# Sensors.net
KiCad netlist of a schematic drawn in Altium Designer
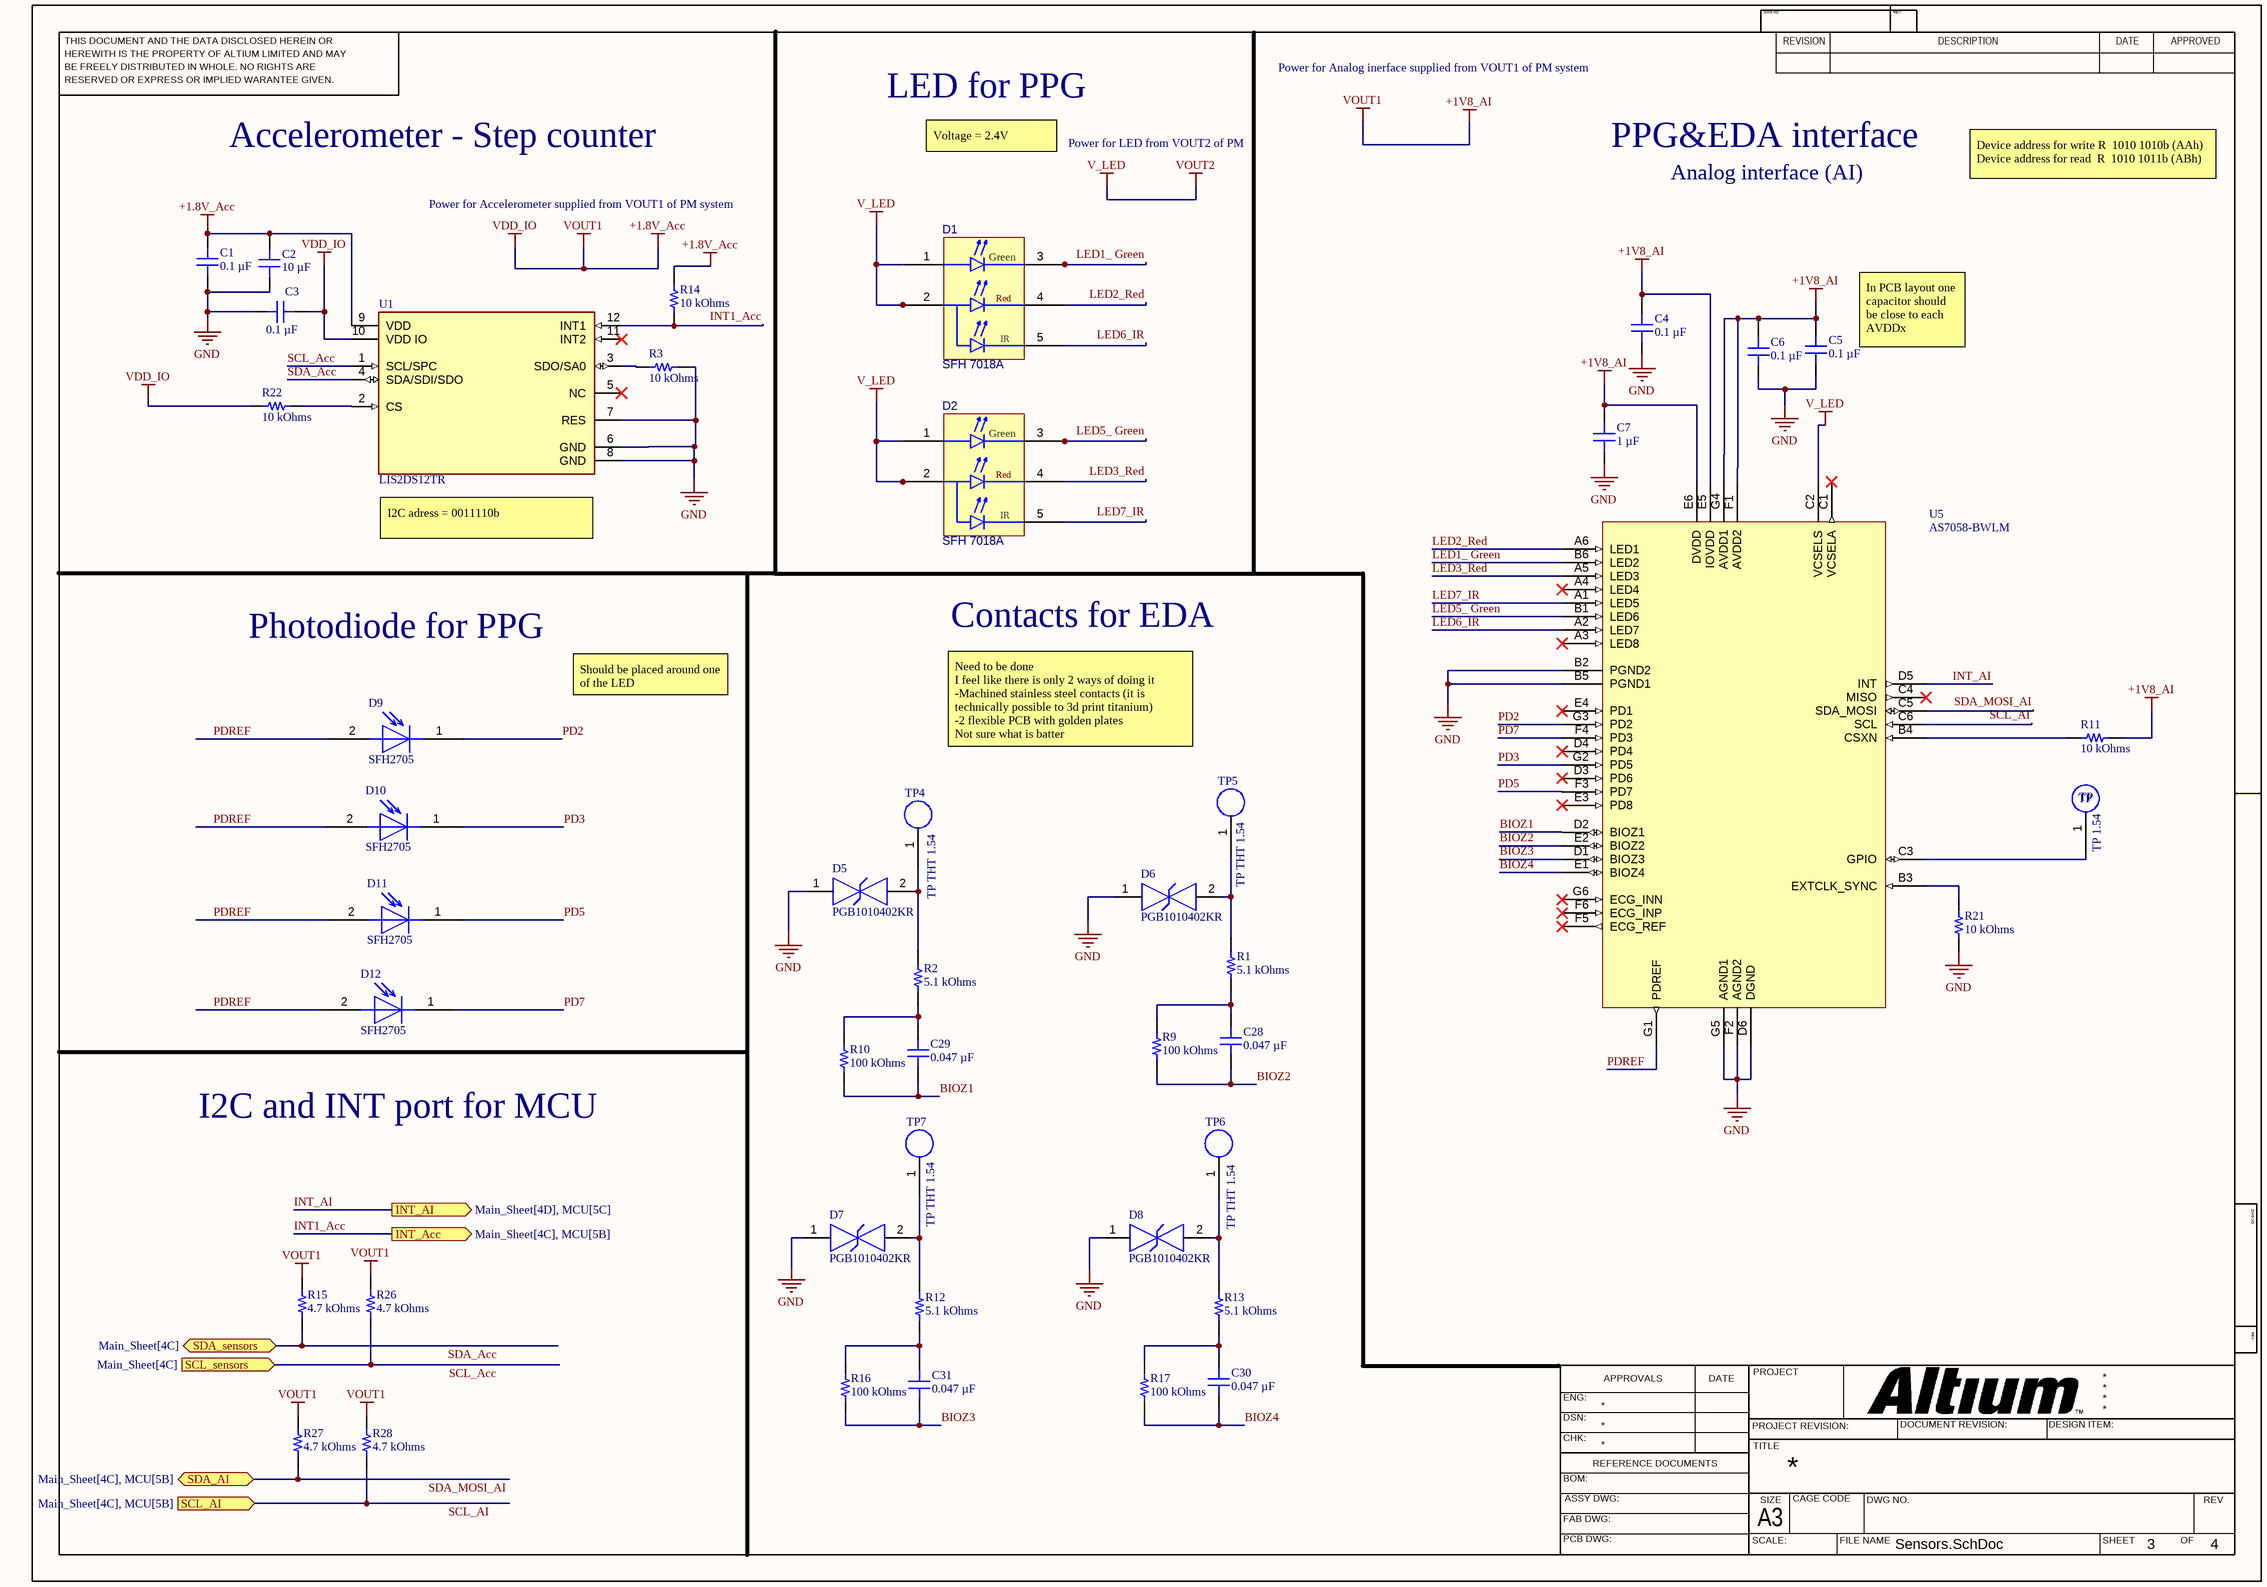
[diagram p0: Sensors.SchDoc]

(export (version "E")
  (design (tool "Eeschema 10.0.6"))
  (components
    (comp (ref "C1")
      (value "0.1 µF")
      (footprint "CAP 0402_1005")
      (description "CAP CER 100NF 10V X7R 0402")
      (fields
        (field (name "PART NUMBER") "CL05B104KP5VPNC")
        (field (name "CAPACITANCE") "0.1 µF")
        (field (name "MANUFACTURER") "Samsung Electro-Mechanics")
      )
      (libsource (lib "Celestial Altium Library - altium_library") (part "Capacitor"))
    )
    (comp (ref "C2")
      (value "10 µF")
      (footprint "CAP 0402_1005")
      (description "CAP CER 10UF 10V X5R 0402")
      (fields
        (field (name "PART NUMBER") "CL05A106MP8NUB8")
        (field (name "CAPACITANCE") "10 µF")
        (field (name "MANUFACTURER") "Samsung Electro-Mechanics")
      )
      (libsource (lib "Celestial Altium Library - altium_library") (part "Capacitor"))
    )
    (comp (ref "C3")
      (value "0.1 µF")
      (footprint "CAP 0402_1005")
      (description "CAP CER 100NF 10V X7R 0402")
      (fields
        (field (name "PART NUMBER") "CL05B104KP5VPNC")
        (field (name "CAPACITANCE") "0.1 µF")
        (field (name "MANUFACTURER") "Samsung Electro-Mechanics")
      )
      (libsource (lib "Celestial Altium Library - altium_library") (part "Capacitor"))
    )
    (comp (ref "C4")
      (value "0.1 µF")
      (footprint "CAP 0402_1005")
      (description "CAP CER 100NF 10V X7R 0402")
      (fields
        (field (name "PART NUMBER") "CL05B104KP5VPNC")
        (field (name "CAPACITANCE") "0.1 µF")
        (field (name "MANUFACTURER") "Samsung Electro-Mechanics")
      )
      (libsource (lib "Celestial Altium Library - altium_library") (part "Capacitor"))
    )
    (comp (ref "C5")
      (value "0.1 µF")
      (footprint "CAP 0402_1005")
      (description "CAP CER 100NF 10V X7R 0402")
      (fields
        (field (name "PART NUMBER") "CL05B104KP5VPNC")
        (field (name "CAPACITANCE") "0.1 µF")
        (field (name "MANUFACTURER") "Samsung Electro-Mechanics")
      )
      (libsource (lib "Celestial Altium Library - altium_library") (part "Capacitor"))
    )
    (comp (ref "C6")
      (value "0.1 µF")
      (footprint "CAP 0402_1005")
      (description "CAP CER 100NF 10V X7R 0402")
      (fields
        (field (name "PART NUMBER") "CL05B104KP5VPNC")
        (field (name "CAPACITANCE") "0.1 µF")
        (field (name "MANUFACTURER") "Samsung Electro-Mechanics")
      )
      (libsource (lib "Celestial Altium Library - altium_library") (part "Capacitor"))
    )
    (comp (ref "C7")
      (value "1 µF")
      (footprint "CAP 0402_1005")
      (description "CAP CER 1UF 10V X5R 0402")
      (fields
        (field (name "PART NUMBER") "885012105012")
        (field (name "CAPACITANCE") "1 µF")
        (field (name "MANUFACTURER") "Würth Elektronik")
      )
      (libsource (lib "Celestial Altium Library - altium_library") (part "Capacitor"))
    )
    (comp (ref "C28")
      (value "0.047 µF")
      (footprint "CAP 0402_1005")
      (description "CAP CER 0402 47NF 25V X7R 10%")
      (fields
        (field (name "PART NUMBER") "C0402C473K3REC7867")
        (field (name "CAPACITANCE") "0.047 µF")
        (field (name "MANUFACTURER") "KEMET")
      )
      (libsource (lib "Celestial Altium Library - altium_library") (part "Capacitor"))
    )
    (comp (ref "C29")
      (value "0.047 µF")
      (footprint "CAP 0402_1005")
      (description "CAP CER 0402 47NF 25V X7R 10%")
      (fields
        (field (name "PART NUMBER") "C0402C473K3REC7867")
        (field (name "CAPACITANCE") "0.047 µF")
        (field (name "MANUFACTURER") "KEMET")
      )
      (libsource (lib "Celestial Altium Library - altium_library") (part "Capacitor"))
    )
    (comp (ref "C30")
      (value "0.047 µF")
      (footprint "CAP 0402_1005")
      (description "CAP CER 0402 47NF 25V X7R 10%")
      (fields
        (field (name "PART NUMBER") "C0402C473K3REC7867")
        (field (name "CAPACITANCE") "0.047 µF")
        (field (name "MANUFACTURER") "KEMET")
      )
      (libsource (lib "Celestial Altium Library - altium_library") (part "Capacitor"))
    )
    (comp (ref "C31")
      (value "0.047 µF")
      (footprint "CAP 0402_1005")
      (description "CAP CER 0402 47NF 25V X7R 10%")
      (fields
        (field (name "PART NUMBER") "C0402C473K3REC7867")
        (field (name "CAPACITANCE") "0.047 µF")
        (field (name "MANUFACTURER") "KEMET")
      )
      (libsource (lib "Celestial Altium Library - altium_library") (part "Capacitor"))
    )
    (comp (ref "D1")
      (value "SFH 7018A")
      (footprint "SFH 7018A-Footprint-1")
      (description "Led, Hr/ir/tg, 655/940/532NM, 120DEG Rohs Compliant: Yes")
      (libsource (lib "Kiryl Alsheuski") (part "DIODE-LED-2"))
    )
    (comp (ref "D2")
      (value "SFH 7018A")
      (footprint "SFH 7018A-Footprint-1")
      (description "Led, Hr/ir/tg, 655/940/532NM, 120DEG Rohs Compliant: Yes")
      (libsource (lib "Kiryl Alsheuski") (part "DIODE-LED-2"))
    )
    (comp (ref "D5")
      (value "PGB1010402KR")
      (footprint "FP-PGB1-0402-MFG")
      (description "TVS DIODE 12V 250V 0402")
      (fields
        (field (name "OCTOPART") "https://octopart.com/pgb1010402kr-littelfuse-10444990")
        (field (name "MANUFACTURER") "Littelfuse")
      )
      (libsource (lib "Altium Content Vault") (part "876f4347bf90aa6f500f43e3cd03972"))
    )
    (comp (ref "D6")
      (value "PGB1010402KR")
      (footprint "FP-PGB1-0402-MFG")
      (description "TVS DIODE 12V 250V 0402")
      (fields
        (field (name "OCTOPART") "https://octopart.com/pgb1010402kr-littelfuse-10444990")
        (field (name "MANUFACTURER") "Littelfuse")
      )
      (libsource (lib "Altium Content Vault") (part "876f4347bf90aa6f500f43e3cd03972"))
    )
    (comp (ref "D7")
      (value "PGB1010402KR")
      (footprint "FP-PGB1-0402-MFG")
      (description "TVS DIODE 12V 250V 0402")
      (fields
        (field (name "OCTOPART") "https://octopart.com/pgb1010402kr-littelfuse-10444990")
        (field (name "MANUFACTURER") "Littelfuse")
      )
      (libsource (lib "Altium Content Vault") (part "876f4347bf90aa6f500f43e3cd03972"))
    )
    (comp (ref "D8")
      (value "PGB1010402KR")
      (footprint "FP-PGB1-0402-MFG")
      (description "TVS DIODE 12V 250V 0402")
      (fields
        (field (name "OCTOPART") "https://octopart.com/pgb1010402kr-littelfuse-10444990")
        (field (name "MANUFACTURER") "Littelfuse")
      )
      (libsource (lib "Altium Content Vault") (part "876f4347bf90aa6f500f43e3cd03972"))
    )
    (comp (ref "D9")
      (value "SFH2705")
      (footprint "DFN175P215X60-2N")
      (description "Photodiode with wide range of wavelength")
      (libsource (lib "Kiryl Alsheuski") (part "SFH2705-Symbol-1"))
    )
    (comp (ref "D10")
      (value "SFH2705")
      (footprint "DFN175P215X60-2N")
      (description "Photodiode with wide range of wavelength")
      (libsource (lib "Kiryl Alsheuski") (part "SFH2705-Symbol-1"))
    )
    (comp (ref "D11")
      (value "SFH2705")
      (footprint "DFN175P215X60-2N")
      (description "Photodiode with wide range of wavelength")
      (libsource (lib "Kiryl Alsheuski") (part "SFH2705-Symbol-1"))
    )
    (comp (ref "D12")
      (value "SFH2705")
      (footprint "DFN175P215X60-2N")
      (description "Photodiode with wide range of wavelength")
      (libsource (lib "Kiryl Alsheuski") (part "SFH2705-Symbol-1"))
    )
    (comp (ref "R1")
      (value "5.1 kOhms")
      (footprint "RES 0402_1005")
      (description "RES 5.1K OHM 1% 1/4W 0402")
      (fields
        (field (name "PART NUMBER") "ERJ-PA2F5101X")
        (field (name "MANUFACTURER") "Panasonic Electronic Components")
      )
      (libsource (lib "Celestial Altium Library - altium_library") (part "Resistor"))
    )
    (comp (ref "R2")
      (value "5.1 kOhms")
      (footprint "RES 0402_1005")
      (description "RES 5.1K OHM 1% 1/4W 0402")
      (fields
        (field (name "PART NUMBER") "ERJ-PA2F5101X")
        (field (name "MANUFACTURER") "Panasonic Electronic Components")
      )
      (libsource (lib "Celestial Altium Library - altium_library") (part "Resistor"))
    )
    (comp (ref "R3")
      (value "10 kOhms")
      (footprint "RES 0402_1005")
      (description "RES 10K OHM 0.1% 1/10W 0402")
      (fields
        (field (name "PART NUMBER") "RP73PF1E10KBTD")
        (field (name "MANUFACTURER") "TE Connectivity Passive Product")
      )
      (libsource (lib "Celestial Altium Library - altium_library") (part "Resistor"))
    )
    (comp (ref "R9")
      (value "100 kOhms")
      (footprint "YAGEO RES 0402_1005")
      (description "RES 100K OHM 1% 1/5W 0402")
      (fields (field (name "PART NUMBER") "SR0402FR-7T100KL") (field (name "MANUFACTURER") "Yageo"))
      (libsource (lib "Celestial Altium Library - altium_library") (part "Resistor"))
    )
    (comp (ref "R10")
      (value "100 kOhms")
      (footprint "YAGEO RES 0402_1005")
      (description "RES 100K OHM 1% 1/5W 0402")
      (fields (field (name "PART NUMBER") "SR0402FR-7T100KL") (field (name "MANUFACTURER") "Yageo"))
      (libsource (lib "Celestial Altium Library - altium_library") (part "Resistor"))
    )
    (comp (ref "R11")
      (value "10 kOhms")
      (footprint "RES 0402_1005")
      (description "RES 10K OHM 0.1% 1/10W 0402")
      (fields
        (field (name "PART NUMBER") "RP73PF1E10KBTD")
        (field (name "MANUFACTURER") "TE Connectivity Passive Product")
      )
      (libsource (lib "Celestial Altium Library - altium_library") (part "Resistor"))
    )
    (comp (ref "R12")
      (value "5.1 kOhms")
      (footprint "RES 0402_1005")
      (description "RES 5.1K OHM 1% 1/4W 0402")
      (fields
        (field (name "PART NUMBER") "ERJ-PA2F5101X")
        (field (name "MANUFACTURER") "Panasonic Electronic Components")
      )
      (libsource (lib "Celestial Altium Library - altium_library") (part "Resistor"))
    )
    (comp (ref "R13")
      (value "5.1 kOhms")
      (footprint "RES 0402_1005")
      (description "RES 5.1K OHM 1% 1/4W 0402")
      (fields
        (field (name "PART NUMBER") "ERJ-PA2F5101X")
        (field (name "MANUFACTURER") "Panasonic Electronic Components")
      )
      (libsource (lib "Celestial Altium Library - altium_library") (part "Resistor"))
    )
    (comp (ref "R14")
      (value "10 kOhms")
      (footprint "RES 0402_1005")
      (description "RES 10K OHM 0.1% 1/10W 0402")
      (fields
        (field (name "PART NUMBER") "RP73PF1E10KBTD")
        (field (name "MANUFACTURER") "TE Connectivity Passive Product")
      )
      (libsource (lib "Celestial Altium Library - altium_library") (part "Resistor"))
    )
    (comp (ref "R15")
      (value "4.7 kOhms")
      (footprint "YAGEO RES 0402_1005")
      (description "RES SMD 4.7K OHM 1% 1/16W 0402")
      (fields (field (name "PART NUMBER") "RT0402FRE074K7L") (field (name "MANUFACTURER") "Yageo"))
      (libsource (lib "Celestial Altium Library - altium_library") (part "Resistor"))
    )
    (comp (ref "R16")
      (value "100 kOhms")
      (footprint "YAGEO RES 0402_1005")
      (description "RES 100K OHM 1% 1/5W 0402")
      (fields (field (name "PART NUMBER") "SR0402FR-7T100KL") (field (name "MANUFACTURER") "Yageo"))
      (libsource (lib "Celestial Altium Library - altium_library") (part "Resistor"))
    )
    (comp (ref "R17")
      (value "100 kOhms")
      (footprint "YAGEO RES 0402_1005")
      (description "RES 100K OHM 1% 1/5W 0402")
      (fields (field (name "PART NUMBER") "SR0402FR-7T100KL") (field (name "MANUFACTURER") "Yageo"))
      (libsource (lib "Celestial Altium Library - altium_library") (part "Resistor"))
    )
    (comp (ref "R21")
      (value "10 kOhms")
      (footprint "RES 0402_1005")
      (description "RES 10K OHM 0.1% 1/10W 0402")
      (fields
        (field (name "PART NUMBER") "RP73PF1E10KBTD")
        (field (name "MANUFACTURER") "TE Connectivity Passive Product")
      )
      (libsource (lib "Celestial Altium Library - altium_library") (part "Resistor"))
    )
    (comp (ref "R22")
      (value "10 kOhms")
      (footprint "RES 0402_1005")
      (description "RES 10K OHM 0.1% 1/10W 0402")
      (fields
        (field (name "PART NUMBER") "RP73PF1E10KBTD")
        (field (name "MANUFACTURER") "TE Connectivity Passive Product")
      )
      (libsource (lib "Celestial Altium Library - altium_library") (part "Resistor"))
    )
    (comp (ref "R26")
      (value "4.7 kOhms")
      (footprint "YAGEO RES 0402_1005")
      (description "RES SMD 4.7K OHM 1% 1/16W 0402")
      (fields (field (name "PART NUMBER") "RT0402FRE074K7L") (field (name "MANUFACTURER") "Yageo"))
      (libsource (lib "Celestial Altium Library - altium_library") (part "Resistor"))
    )
    (comp (ref "R27")
      (value "4.7 kOhms")
      (footprint "YAGEO RES 0402_1005")
      (description "RES SMD 4.7K OHM 1% 1/16W 0402")
      (fields (field (name "PART NUMBER") "RT0402FRE074K7L") (field (name "MANUFACTURER") "Yageo"))
      (libsource (lib "Celestial Altium Library - altium_library") (part "Resistor"))
    )
    (comp (ref "R28")
      (value "4.7 kOhms")
      (footprint "YAGEO RES 0402_1005")
      (description "RES SMD 4.7K OHM 1% 1/16W 0402")
      (fields (field (name "PART NUMBER") "RT0402FRE074K7L") (field (name "MANUFACTURER") "Yageo"))
      (libsource (lib "Celestial Altium Library - altium_library") (part "Resistor"))
    )
    (comp (ref "TP")
      (value "TP 1.54")
      (footprint "TP-Footprint-1")
      (description "Rounded rectangular pad 1.54mm")
      (libsource (lib "Kiryl Alsheuski") (part "TP-Symbol-1"))
    )
    (comp (ref "TP4")
      (value "TP THT 1.54")
      (footprint "TP-Footprint-1")
      (description "Test pint THT round via 1.54mm pad 1mm hole")
      (libsource (lib "") (part "TP-Symbol-1_1"))
    )
    (comp (ref "TP5")
      (value "TP THT 1.54")
      (footprint "TP-Footprint-1")
      (description "Test pint THT round via 1.54mm pad 1mm hole")
      (libsource (lib "") (part "TP-Symbol-1_1"))
    )
    (comp (ref "TP6")
      (value "TP THT 1.54")
      (footprint "TP-Footprint-1")
      (description "Test pint THT round via 1.54mm pad 1mm hole")
      (libsource (lib "") (part "TP-Symbol-1_1"))
    )
    (comp (ref "TP7")
      (value "TP THT 1.54")
      (footprint "TP-Footprint-1")
      (description "Test pint THT round via 1.54mm pad 1mm hole")
      (libsource (lib "") (part "TP-Symbol-1_1"))
    )
    (comp (ref "U1")
      (value "LIS2DS12TR")
      (footprint "FP-LGA12_8566956-MFG")
      (description "ACCEL 2-16G I2C/SPI 12LGA")
      (libsource (lib "Altium Content Vault") (part "71777070b7db0ed8ebb1a0f678b9644"))
    )
    (comp (ref "U5")
      (value "AS7058-BWLM")
      (footprint "BGA42C40P6X7_254X282X60")
      (description "AS7058 Series 1.8 V PPG/ECG/BioZ/EDA Vital Sign Monitoring IC - WLCSP-42")
      (libsource (lib "Kiryl Alsheuski") (part "AS7058-BWLM-Symbol-1"))
    )
  )
  (nets
    (net (code "1") (name "+1.8V_Acc") (class "Default")
      (node (ref "C1") (pin "2") (pinfunction "2_2") (pintype "passive"))
      (node (ref "C2") (pin "2") (pinfunction "2_2") (pintype "passive"))
      (node (ref "C3") (pin "1") (pinfunction "1_1") (pintype "passive"))
      (node (ref "C4") (pin "2") (pinfunction "2_2") (pintype "passive"))
      (node (ref "C5") (pin "2") (pinfunction "2_2") (pintype "passive"))
      (node (ref "C6") (pin "2") (pinfunction "2_2") (pintype "passive"))
      (node (ref "C7") (pin "2") (pinfunction "2_2") (pintype "passive"))
      (node (ref "R11") (pin "2") (pinfunction "2_2") (pintype "passive"))
      (node (ref "R14") (pin "2") (pinfunction "2_2") (pintype "passive"))
      (node (ref "R15") (pin "2") (pinfunction "2_2") (pintype "passive"))
      (node (ref "R22") (pin "1") (pinfunction "1_1") (pintype "passive"))
      (node (ref "R26") (pin "2") (pinfunction "2_2") (pintype "passive"))
      (node (ref "R27") (pin "2") (pinfunction "2_2") (pintype "passive"))
      (node (ref "R28") (pin "2") (pinfunction "2_2") (pintype "passive"))
      (node (ref "U1") (pin "10") (pinfunction "VDD_IO_10") (pintype "power_in"))
      (node (ref "U1") (pin "9") (pinfunction "VDD_9") (pintype "power_in"))
      (node (ref "U5") (pin "E5") (pinfunction "IOVDD_E5") (pintype "power_in"))
      (node (ref "U5") (pin "E6") (pinfunction "DVDD_E6") (pintype "power_in"))
      (node (ref "U5") (pin "F1") (pinfunction "AVDD2_F1") (pintype "power_in"))
      (node (ref "U5") (pin "G4") (pinfunction "AVDD1_G4") (pintype "power_in"))
    )
    (net (code "2") (name "/BIOZ1") (class "Default")
      (node (ref "C29") (pin "1") (pinfunction "1_1") (pintype "passive"))
      (node (ref "R10") (pin "1") (pinfunction "1_1") (pintype "passive"))
      (node (ref "U5") (pin "D2") (pinfunction "BIOZ1_D2") (pintype "bidirectional"))
    )
    (net (code "3") (name "/BIOZ2") (class "Default")
      (node (ref "C28") (pin "1") (pinfunction "1_1") (pintype "passive"))
      (node (ref "R9") (pin "1") (pinfunction "1_1") (pintype "passive"))
      (node (ref "U5") (pin "E2") (pinfunction "BIOZ2_E2") (pintype "bidirectional"))
    )
    (net (code "4") (name "/BIOZ3") (class "Default")
      (node (ref "C31") (pin "1") (pinfunction "1_1") (pintype "passive"))
      (node (ref "R16") (pin "1") (pinfunction "1_1") (pintype "passive"))
      (node (ref "U5") (pin "D1") (pinfunction "BIOZ3_D1") (pintype "bidirectional"))
    )
    (net (code "5") (name "/BIOZ4") (class "Default")
      (node (ref "C30") (pin "1") (pinfunction "1_1") (pintype "passive"))
      (node (ref "R17") (pin "1") (pinfunction "1_1") (pintype "passive"))
      (node (ref "U5") (pin "E1") (pinfunction "BIOZ4_E1") (pintype "bidirectional"))
    )
    (net (code "6") (name "/INT1_Acc") (class "Default")
      (node (ref "R14") (pin "1") (pinfunction "1_1") (pintype "passive"))
      (node (ref "U1") (pin "12") (pinfunction "INT1_12") (pintype "input"))
    )
    (net (code "7") (name "/INT_AI") (class "Default")
      (node (ref "U5") (pin "D5") (pinfunction "INT_D5") (pintype "output"))
    )
    (net (code "8") (name "/LED1_ Green") (class "Default")
      (node (ref "D1") (pin "3") (pinfunction "3_3") (pintype "passive"))
      (node (ref "D1") (pin "7") (pinfunction "7_7") (pintype "passive"))
      (node (ref "D1") (pin "8") (pinfunction "8_8") (pintype "passive"))
      (node (ref "U5") (pin "B6") (pinfunction "LED2_B6") (pintype "input"))
    )
    (net (code "9") (name "/LED2_Red") (class "Default")
      (node (ref "D1") (pin "4") (pinfunction "4_4") (pintype "passive"))
      (node (ref "U5") (pin "A6") (pinfunction "LED1_A6") (pintype "input"))
    )
    (net (code "10") (name "/LED3_Red") (class "Default")
      (node (ref "D2") (pin "4") (pinfunction "4_4") (pintype "passive"))
      (node (ref "U5") (pin "A5") (pinfunction "LED3_A5") (pintype "input"))
    )
    (net (code "11") (name "/LED5_ Green") (class "Default")
      (node (ref "D2") (pin "3") (pinfunction "3_3") (pintype "passive"))
      (node (ref "D2") (pin "7") (pinfunction "7_7") (pintype "passive"))
      (node (ref "D2") (pin "8") (pinfunction "8_8") (pintype "passive"))
      (node (ref "U5") (pin "B1") (pinfunction "LED6_B1") (pintype "input"))
    )
    (net (code "12") (name "/LED6_IR") (class "Default")
      (node (ref "D1") (pin "5") (pinfunction "5_5") (pintype "passive"))
      (node (ref "U5") (pin "A2") (pinfunction "LED7_A2") (pintype "input"))
    )
    (net (code "13") (name "/LED7_IR") (class "Default")
      (node (ref "D2") (pin "5") (pinfunction "5_5") (pintype "passive"))
      (node (ref "U5") (pin "A1") (pinfunction "LED5_A1") (pintype "input"))
    )
    (net (code "14") (name "/PD2") (class "Default")
      (node (ref "D9") (pin "1") (pinfunction "1_1") (pintype "passive"))
      (node (ref "U5") (pin "G3") (pinfunction "PD2_G3") (pintype "input"))
    )
    (net (code "15") (name "/PD3") (class "Default")
      (node (ref "D10") (pin "1") (pinfunction "1_1") (pintype "passive"))
      (node (ref "U5") (pin "G2") (pinfunction "PD5_G2") (pintype "input"))
    )
    (net (code "16") (name "/PD5") (class "Default")
      (node (ref "D11") (pin "1") (pinfunction "1_1") (pintype "passive"))
      (node (ref "U5") (pin "F3") (pinfunction "PD7_F3") (pintype "input"))
    )
    (net (code "17") (name "/PD7") (class "Default")
      (node (ref "D12") (pin "1") (pinfunction "1_1") (pintype "passive"))
      (node (ref "U5") (pin "F4") (pinfunction "PD3_F4") (pintype "input"))
    )
    (net (code "18") (name "/PDREF") (class "Default")
      (node (ref "D10") (pin "2") (pinfunction "2_2") (pintype "passive"))
      (node (ref "D11") (pin "2") (pinfunction "2_2") (pintype "passive"))
      (node (ref "D12") (pin "2") (pinfunction "2_2") (pintype "passive"))
      (node (ref "D9") (pin "2") (pinfunction "2_2") (pintype "passive"))
      (node (ref "U5") (pin "G1") (pinfunction "PDREF_G1") (pintype "output"))
    )
    (net (code "19") (name "/SCL_AI") (class "Default")
      (node (ref "R28") (pin "1") (pinfunction "1_1") (pintype "passive"))
      (node (ref "U5") (pin "C6") (pinfunction "SCL_C6") (pintype "input"))
    )
    (net (code "20") (name "/SCL_Acc") (class "Default")
      (node (ref "R26") (pin "1") (pinfunction "1_1") (pintype "passive"))
      (node (ref "U1") (pin "1") (pinfunction "SCL/SPC_1") (pintype "input"))
    )
    (net (code "21") (name "/SDA_Acc") (class "Default")
      (node (ref "R15") (pin "1") (pinfunction "1_1") (pintype "passive"))
      (node (ref "U1") (pin "4") (pinfunction "SDA/SDI/SDO_4") (pintype "bidirectional"))
    )
    (net (code "22") (name "/SDA_MOSI_AI") (class "Default")
      (node (ref "R27") (pin "1") (pinfunction "1_1") (pintype "passive"))
      (node (ref "U5") (pin "C5") (pinfunction "SDA_MOSI_C5") (pintype "bidirectional"))
    )
    (net (code "23") (name "GND") (class "Default")
      (node (ref "C1") (pin "1") (pinfunction "1_1") (pintype "passive"))
      (node (ref "C2") (pin "1") (pinfunction "1_1") (pintype "passive"))
      (node (ref "C3") (pin "2") (pinfunction "2_2") (pintype "passive"))
      (node (ref "C4") (pin "1") (pinfunction "1_1") (pintype "passive"))
      (node (ref "C5") (pin "1") (pinfunction "1_1") (pintype "passive"))
      (node (ref "C6") (pin "1") (pinfunction "1_1") (pintype "passive"))
      (node (ref "C7") (pin "1") (pinfunction "1_1") (pintype "passive"))
      (node (ref "D5") (pin "1") (pinfunction "1_1") (pintype "passive"))
      (node (ref "D6") (pin "1") (pinfunction "1_1") (pintype "passive"))
      (node (ref "D7") (pin "1") (pinfunction "1_1") (pintype "passive"))
      (node (ref "D8") (pin "1") (pinfunction "1_1") (pintype "passive"))
      (node (ref "R21") (pin "1") (pinfunction "1_1") (pintype "passive"))
      (node (ref "R3") (pin "2") (pinfunction "2_2") (pintype "passive"))
      (node (ref "U1") (pin "6") (pinfunction "GND_6") (pintype "power_in"))
      (node (ref "U1") (pin "7") (pinfunction "RES_7") (pintype "power_in"))
      (node (ref "U1") (pin "8") (pinfunction "GND_8") (pintype "power_in"))
      (node (ref "U5") (pin "B2") (pinfunction "PGND2_B2") (pintype "power_in"))
      (node (ref "U5") (pin "B5") (pinfunction "PGND1_B5") (pintype "power_in"))
      (node (ref "U5") (pin "D6") (pinfunction "DGND_D6") (pintype "power_in"))
      (node (ref "U5") (pin "F2") (pinfunction "AGND2_F2") (pintype "power_in"))
      (node (ref "U5") (pin "G5") (pinfunction "AGND1_G5") (pintype "power_in"))
    )
    (net (code "24") (name "Net-(C28-Pad2)") (class "Default")
      (node (ref "C28") (pin "2") (pinfunction "2_2") (pintype "passive"))
      (node (ref "R1") (pin "1") (pinfunction "1_1") (pintype "passive"))
      (node (ref "R9") (pin "2") (pinfunction "2_2") (pintype "passive"))
    )
    (net (code "25") (name "Net-(C29-Pad2)") (class "Default")
      (node (ref "C29") (pin "2") (pinfunction "2_2") (pintype "passive"))
      (node (ref "R10") (pin "2") (pinfunction "2_2") (pintype "passive"))
      (node (ref "R2") (pin "1") (pinfunction "1_1") (pintype "passive"))
    )
    (net (code "26") (name "Net-(C30-Pad2)") (class "Default")
      (node (ref "C30") (pin "2") (pinfunction "2_2") (pintype "passive"))
      (node (ref "R13") (pin "1") (pinfunction "1_1") (pintype "passive"))
      (node (ref "R17") (pin "2") (pinfunction "2_2") (pintype "passive"))
    )
    (net (code "27") (name "Net-(C31-Pad2)") (class "Default")
      (node (ref "C31") (pin "2") (pinfunction "2_2") (pintype "passive"))
      (node (ref "R12") (pin "1") (pinfunction "1_1") (pintype "passive"))
      (node (ref "R16") (pin "2") (pinfunction "2_2") (pintype "passive"))
    )
    (net (code "28") (name "Net-(D5-Pad2)") (class "Default")
      (node (ref "D5") (pin "2") (pinfunction "2_2") (pintype "passive"))
      (node (ref "R2") (pin "2") (pinfunction "2_2") (pintype "passive"))
      (node (ref "TP4") (pin "1") (pinfunction "1_1") (pintype "passive"))
    )
    (net (code "29") (name "Net-(D6-Pad2)") (class "Default")
      (node (ref "D6") (pin "2") (pinfunction "2_2") (pintype "passive"))
      (node (ref "R1") (pin "2") (pinfunction "2_2") (pintype "passive"))
      (node (ref "TP5") (pin "1") (pinfunction "1_1") (pintype "passive"))
    )
    (net (code "30") (name "Net-(D7-Pad2)") (class "Default")
      (node (ref "D7") (pin "2") (pinfunction "2_2") (pintype "passive"))
      (node (ref "R12") (pin "2") (pinfunction "2_2") (pintype "passive"))
      (node (ref "TP7") (pin "1") (pinfunction "1_1") (pintype "passive"))
    )
    (net (code "31") (name "Net-(D8-Pad2)") (class "Default")
      (node (ref "D8") (pin "2") (pinfunction "2_2") (pintype "passive"))
      (node (ref "R13") (pin "2") (pinfunction "2_2") (pintype "passive"))
      (node (ref "TP6") (pin "1") (pinfunction "1_1") (pintype "passive"))
    )
    (net (code "32") (name "Net-(U1-CS)") (class "Default")
      (node (ref "R22") (pin "2") (pinfunction "2_2") (pintype "passive"))
      (node (ref "U1") (pin "2") (pinfunction "CS_2") (pintype "input"))
    )
    (net (code "33") (name "Net-(U1-SDO{slash}SA0)") (class "Default")
      (node (ref "R3") (pin "1") (pinfunction "1_1") (pintype "passive"))
      (node (ref "U1") (pin "3") (pinfunction "SDO/SA0_3") (pintype "bidirectional"))
    )
    (net (code "34") (name "Net-(U5-CSXN)") (class "Default")
      (node (ref "R11") (pin "1") (pinfunction "1_1") (pintype "passive"))
      (node (ref "U5") (pin "B4") (pinfunction "CSXN_B4") (pintype "input"))
    )
    (net (code "35") (name "Net-(U5-EXTCLK_SYNC)") (class "Default")
      (node (ref "R21") (pin "2") (pinfunction "2_2") (pintype "passive"))
      (node (ref "U5") (pin "B3") (pinfunction "EXTCLK_SYNC_B3") (pintype "input"))
    )
    (net (code "36") (name "Net-(U5-GPIO)") (class "Default")
      (node (ref "TP") (pin "1") (pinfunction "1_1") (pintype "passive"))
      (node (ref "U5") (pin "C3") (pinfunction "GPIO_C3") (pintype "bidirectional"))
    )
    (net (code "37") (name "VOUT2") (class "Default")
      (node (ref "D1") (pin "1") (pinfunction "1_1") (pintype "passive"))
      (node (ref "D1") (pin "2") (pinfunction "2_2") (pintype "passive"))
      (node (ref "D1") (pin "6") (pinfunction "6_6") (pintype "passive"))
      (node (ref "D2") (pin "1") (pinfunction "1_1") (pintype "passive"))
      (node (ref "D2") (pin "2") (pinfunction "2_2") (pintype "passive"))
      (node (ref "D2") (pin "6") (pinfunction "6_6") (pintype "passive"))
      (node (ref "U5") (pin "C2") (pinfunction "VCSELS_C2") (pintype "power_in"))
    )
    (net (code "38") (name "unconnected-(U1-INT2-Pad11)") (class "Default")
      (node (ref "U1") (pin "11") (pinfunction "INT2_11") (pintype "input+no_connect"))
    )
    (net (code "39") (name "unconnected-(U1-NC-Pad5)") (class "Default")
      (node (ref "U1") (pin "5") (pinfunction "NC_5") (pintype "passive+no_connect"))
    )
    (net (code "40") (name "unconnected-(U5-ECG_INN-PadG6)") (class "Default")
      (node (ref "U5") (pin "G6") (pinfunction "ECG_INN_G6") (pintype "input+no_connect"))
    )
    (net (code "41") (name "unconnected-(U5-ECG_INP-PadF6)") (class "Default")
      (node (ref "U5") (pin "F6") (pinfunction "ECG_INP_F6") (pintype "input+no_connect"))
    )
    (net (code "42") (name "unconnected-(U5-ECG_REF-PadF5)") (class "Default")
      (node (ref "U5") (pin "F5") (pinfunction "ECG_REF_F5") (pintype "output+no_connect"))
    )
    (net (code "43") (name "unconnected-(U5-LED4-PadA4)") (class "Default")
      (node (ref "U5") (pin "A4") (pinfunction "LED4_A4") (pintype "input+no_connect"))
    )
    (net (code "44") (name "unconnected-(U5-LED8-PadA3)") (class "Default")
      (node (ref "U5") (pin "A3") (pinfunction "LED8_A3") (pintype "input+no_connect"))
    )
    (net (code "45") (name "unconnected-(U5-MISO-PadC4)") (class "Default")
      (node (ref "U5") (pin "C4") (pinfunction "MISO_C4") (pintype "output+no_connect"))
    )
    (net (code "46") (name "unconnected-(U5-PD1-PadE4)") (class "Default")
      (node (ref "U5") (pin "E4") (pinfunction "PD1_E4") (pintype "input+no_connect"))
    )
    (net (code "47") (name "unconnected-(U5-PD4-PadD4)") (class "Default")
      (node (ref "U5") (pin "D4") (pinfunction "PD4_D4") (pintype "input+no_connect"))
    )
    (net (code "48") (name "unconnected-(U5-PD6-PadD3)") (class "Default")
      (node (ref "U5") (pin "D3") (pinfunction "PD6_D3") (pintype "input+no_connect"))
    )
    (net (code "49") (name "unconnected-(U5-PD8-PadE3)") (class "Default")
      (node (ref "U5") (pin "E3") (pinfunction "PD8_E3") (pintype "input+no_connect"))
    )
    (net (code "50") (name "unconnected-(U5-VCSELA-PadC1)") (class "Default")
      (node (ref "U5") (pin "C1") (pinfunction "VCSELA_C1") (pintype "output+no_connect"))
    )
  )
)
